# Avometer_v1_2.net
KiCad netlist of a schematic drawn in Altium Designer
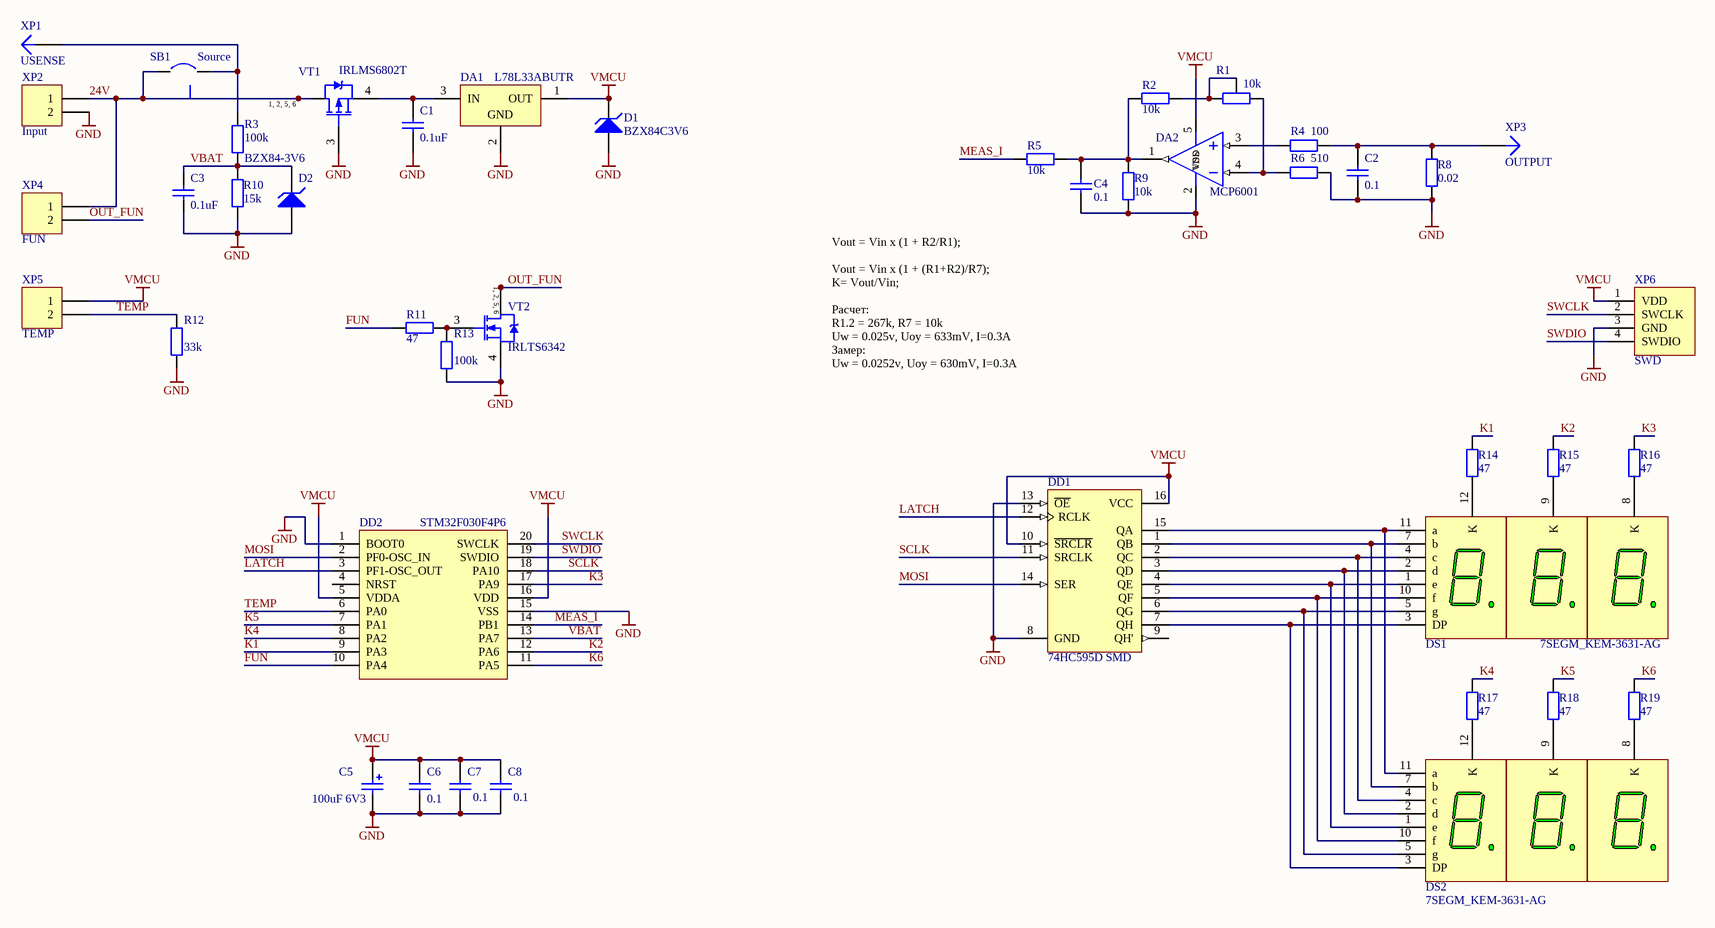
[diagram p0: Avometer v1.2.SchDoc]

(export (version "E")
  (design (tool "Eeschema 10.0.6"))
  (components
    (comp (ref "C1")
      (value "0.1uF")
      (footprint "CAP 0603_N")
      (description "Capacitor SMD")
      (libsource (lib "MyLibrary") (part "CAP_SMD"))
    )
    (comp (ref "C2")
      (value "0.1")
      (footprint "CAP 0603_N")
      (description "Capacitor SMD")
      (libsource (lib "MyLibrary") (part "CAP_SMD"))
    )
    (comp (ref "C3") (value "0.1uF") (footprint "CAP 0603_N") (libsource (lib "") (part "CAP_SMD_1")))
    (comp (ref "C4")
      (value "0.1")
      (footprint "CAP 0603_N")
      (description "Capacitor SMD")
      (libsource (lib "MyLibrary") (part "CAP_SMD"))
    )
    (comp (ref "C5")
      (value "100uF 6V3")
      (footprint "CAP_TANT_B_TYPE_3528-21")
      (description "Capacitor SMD Tantalum")
      (libsource (lib "MyLibrary") (part "CAP_SMD_TANT"))
    )
    (comp (ref "C6")
      (value "0.1")
      (footprint "CAP 0603_N")
      (description "Capacitor SMD")
      (libsource (lib "MyLibrary") (part "CAP_SMD"))
    )
    (comp (ref "C7")
      (value "0.1")
      (footprint "CAP 0603_N")
      (description "Capacitor SMD")
      (libsource (lib "MyLibrary") (part "CAP_SMD"))
    )
    (comp (ref "C8")
      (value "0.1")
      (footprint "CAP 0603_N")
      (description "Capacitor SMD")
      (libsource (lib "MyLibrary") (part "CAP_SMD"))
    )
    (comp (ref "D1")
      (value "BZX84C3V6")
      (footprint "SOT-23_L")
      (description "Zener Diode")
      (fields (field (name "PUBLISHER") "Altium Limited"))
      (libsource (lib "") (part "BZX84_1"))
    )
    (comp (ref "D2")
      (value "BZX84-3V6")
      (footprint "SOT-23_L")
      (description "Zener Diode")
      (fields (field (name "PUBLISHER") "Altium Limited"))
      (libsource (lib "MyLibrary") (part "BZX84"))
    )
    (comp (ref "DA1")
      (value "L78L33ABUTR")
      (footprint "SOT-89")
      (description "Vin=30V Positive Voltage Regulator")
      (fields (field (name "PUBLISHER") "Altium Limited"))
      (libsource (lib "MyLibrary") (part "L78L33ABUTR"))
    )
    (comp (ref "DA2")
      (value "MCP6001")
      (footprint "SOT-23-5_L")
      (description "1 MHz, Low-Power Op Amp")
      (libsource (lib "MyLibrary") (part "MCP6001"))
    )
    (comp (ref "DD1")
      (value "74HC595D SMD")
      (footprint "SOIC-16_L")
      (description "8-Bit Shift Register with 3-State Output Registers")
      (fields (field (name "PUBLISHER") "Altium Limited"))
      (libsource (lib "MyLibrary") (part "74HC595D SMD"))
    )
    (comp (ref "DD2")
      (value "STM32F030F4P6")
      (footprint "TSSOP-20_N")
      (description "Cortex-M0 32-bit MCU, 16 KB Flash, 4 KB Internal RAM, 15 I/Os, 20-pin TSSOP, -40 to 85 degC")
      (libsource (lib "MyLibrary") (part "STM32F030F4P6"))
    )
    (comp (ref "DS1")
      (value "7SEGM_KEM-3631-AG")
      (footprint "7SEGM_KEM-3631-AG_BLUE")
      (description "7.62 mm Black Surface Green 7-Segment Display: CC, RH DP")
      (fields (field (name "PUBLISHER") "Altium Limited"))
      (libsource (lib "MyLibrary") (part "7SEGM_KEM-3631-AG"))
    )
    (comp (ref "DS2")
      (value "7SEGM_KEM-3631-AG")
      (footprint "7SEGM_KEM-3631-AG_RED")
      (description "7.62 mm Black Surface Green 7-Segment Display: CC, RH DP")
      (fields (field (name "PUBLISHER") "Altium Limited"))
      (libsource (lib "MyLibrary") (part "7SEGM_KEM-3631-AG"))
    )
    (comp (ref "R1")
      (value "10k")
      (footprint "RES VAR 1")
      (description "Tapped Resistor")
      (fields (field (name "PUBLISHER") "Altium Limited"))
      (libsource (lib "MyLibrary") (part "RES_SMD_Tap"))
    )
    (comp (ref "R2") (value "10k") (footprint "RES 0603_N") (libsource (lib "") (part "Resistor_SMD_1")))
    (comp (ref "R3") (value "100k") (footprint "RES 0603_N") (libsource (lib "MyLibrary") (part "RES_SMD")))
    (comp (ref "R4") (value "100") (footprint "RES 0603_N") (libsource (lib "") (part "Resistor_SMD_1")))
    (comp (ref "R5")
      (value "10k")
      (footprint "RES 0603_N")
      (description "Resistor")
      (libsource (lib "") (part "RES_SMD_1"))
    )
    (comp (ref "R6") (value "510") (footprint "RES 0603_N") (libsource (lib "") (part "Resistor_SMD_1")))
    (comp (ref "R8")
      (value "0.02")
      (footprint "RES 2512")
      (description "Resistor")
      (libsource (lib "MyLibrary") (part "RES_SMD"))
    )
    (comp (ref "R9") (value "10k") (footprint "RES 0603_N") (libsource (lib "") (part "Resistor_SMD_2")))
    (comp (ref "R10") (value "15k") (footprint "RES 0603_N") (libsource (lib "MyLibrary") (part "RES_SMD")))
    (comp (ref "R11")
      (value "47")
      (footprint "RES 0603_N")
      (description "Chip Resistor")
      (libsource (lib "") (part "RES_SMD_1"))
    )
    (comp (ref "R12")
      (value "33k")
      (footprint "RES 0603_N")
      (description "Chip Resistor")
      (libsource (lib "SyntecoLibrary") (part "RES_SMD"))
    )
    (comp (ref "R13")
      (value "100k")
      (footprint "RES 0603_N")
      (description "Chip Resistor")
      (libsource (lib "SyntecoLibrary") (part "RES_SMD"))
    )
    (comp (ref "R14")
      (value "47")
      (footprint "RES 0603_N")
      (libsource (lib "MyLibrary") (part "Resistor_SMD"))
    )
    (comp (ref "R15")
      (value "47")
      (footprint "RES 0603_N")
      (libsource (lib "MyLibrary") (part "Resistor_SMD"))
    )
    (comp (ref "R16")
      (value "47")
      (footprint "RES 0603_N")
      (libsource (lib "MyLibrary") (part "Resistor_SMD"))
    )
    (comp (ref "R17")
      (value "47")
      (footprint "RES 0603_N")
      (libsource (lib "MyLibrary") (part "Resistor_SMD"))
    )
    (comp (ref "R18")
      (value "47")
      (footprint "RES 0603_N")
      (libsource (lib "MyLibrary") (part "Resistor_SMD"))
    )
    (comp (ref "R19")
      (value "47")
      (footprint "RES 0603_N")
      (libsource (lib "MyLibrary") (part "Resistor_SMD"))
    )
    (comp (ref "SB1")
      (value "Source")
      (footprint "JUMPER_SOLDERED")
      (description "Jumper")
      (libsource (lib "MyLibrary") (part "Jumper_SMD"))
    )
    (comp (ref "VT1")
      (value "IRLMS6802T")
      (footprint "SOT-23-6_L")
      (description "P-Channel MOSFET 20V 4.5A")
      (fields (field (name "PUBLISHER") "Altium Limited"))
      (libsource (lib "MyLibrary") (part "IRLMS6802T"))
    )
    (comp (ref "VT2")
      (value "IRLTS6342")
      (footprint "TSOP-6")
      (description "30V, 6.7A, 1V N-Channel MOSFET")
      (fields (field (name "PUBLISHER") "Altium Limited"))
      (libsource (lib "MyLibrary") (part "IRLTS6342"))
    )
    (comp (ref "XP1")
      (value "USENSE")
      (footprint "CON_PIN")
      (description "Plug papa")
      (fields (field (name "PUBLISHER") "Altium Limited"))
      (libsource (lib "MyLibrary") (part "CON_1x1_PIN"))
    )
    (comp (ref "XP2")
      (value "Input")
      (footprint "CON_5.08MM_1X2")
      (description "Header, 2-Pin")
      (fields (field (name "PUBLISHER") "Altium Limited"))
      (libsource (lib "MyLibrary") (part "CON_5.08mm_1x2"))
    )
    (comp (ref "XP3")
      (value "OUTPUT")
      (footprint "CON_PIN")
      (description "Plug papa")
      (fields (field (name "PUBLISHER") "Altium Limited"))
      (libsource (lib "MyLibrary") (part "CON_1x1_PIN"))
    )
    (comp (ref "XP4")
      (value "FUN")
      (footprint "CON_2.54MM_1X2")
      (description "Header, 2-Pin")
      (fields (field (name "PUBLISHER") "Altium Limited"))
      (libsource (lib "MyLibrary") (part "CON_2.54mm_1x2"))
    )
    (comp (ref "XP5")
      (value "TEMP")
      (footprint "CON_2.54MM_1X2")
      (description "Header, 2-Pin")
      (fields (field (name "PUBLISHER") "Altium Limited"))
      (libsource (lib "MyLibrary") (part "CON_2.54mm_1x2"))
    )
    (comp (ref "XP6")
      (value "SWD")
      (footprint "CON_1.27MM_1X4_SWD")
      (description "Header, 3-Pin")
      (fields (field (name "PUBLISHER") "Altium Limited"))
      (libsource (lib "MyLibrary") (part "CON_1.27mm_1x4_SWD"))
    )
  )
  (nets
    (net (code "1") (name "/24V") (class "Default")
      (node (ref "SB1") (pin "1") (pinfunction "1_1") (pintype "passive"))
      (node (ref "VT1") (pin "1") (pinfunction "D_1") (pintype "passive"))
      (node (ref "VT1") (pin "2") (pinfunction "D_2") (pintype "passive"))
      (node (ref "VT1") (pin "5") (pinfunction "D_5") (pintype "passive"))
      (node (ref "VT1") (pin "6") (pinfunction "D_6") (pintype "passive"))
      (node (ref "XP2") (pin "1") (pinfunction "1_1") (pintype "passive"))
      (node (ref "XP4") (pin "1") (pinfunction "1_1") (pintype "passive"))
    )
    (net (code "2") (name "/FUN") (class "Default")
      (node (ref "DD2") (pin "10") (pinfunction "PA4_10") (pintype "passive"))
      (node (ref "R11") (pin "2") (pinfunction "2_2") (pintype "passive"))
    )
    (net (code "3") (name "/K1") (class "Default")
      (node (ref "DD2") (pin "9") (pinfunction "PA3_9") (pintype "passive"))
      (node (ref "R14") (pin "2") (pinfunction "2_2") (pintype "passive"))
    )
    (net (code "4") (name "/K2") (class "Default")
      (node (ref "DD2") (pin "12") (pinfunction "PA6_12") (pintype "passive"))
      (node (ref "R15") (pin "2") (pinfunction "2_2") (pintype "passive"))
    )
    (net (code "5") (name "/K3") (class "Default")
      (node (ref "DD2") (pin "17") (pinfunction "PA9_17") (pintype "passive"))
      (node (ref "R16") (pin "2") (pinfunction "2_2") (pintype "passive"))
    )
    (net (code "6") (name "/K4") (class "Default")
      (node (ref "DD2") (pin "8") (pinfunction "PA2_8") (pintype "passive"))
      (node (ref "R17") (pin "2") (pinfunction "2_2") (pintype "passive"))
    )
    (net (code "7") (name "/K5") (class "Default")
      (node (ref "DD2") (pin "7") (pinfunction "PA1_7") (pintype "passive"))
      (node (ref "R18") (pin "2") (pinfunction "2_2") (pintype "passive"))
    )
    (net (code "8") (name "/K6") (class "Default")
      (node (ref "DD2") (pin "11") (pinfunction "PA5_11") (pintype "passive"))
      (node (ref "R19") (pin "2") (pinfunction "2_2") (pintype "passive"))
    )
    (net (code "9") (name "/LATCH") (class "Default")
      (node (ref "DD1") (pin "12") (pinfunction "RCLK_12") (pintype "input"))
      (node (ref "DD2") (pin "3") (pinfunction "PF1-OSC_OUT_3") (pintype "passive"))
    )
    (net (code "10") (name "/MEAS_I") (class "Default")
      (node (ref "DD2") (pin "14") (pinfunction "PB1_14") (pintype "passive"))
      (node (ref "R5") (pin "1") (pinfunction "1_1") (pintype "passive"))
    )
    (net (code "11") (name "/MOSI") (class "Default")
      (node (ref "DD1") (pin "14") (pinfunction "SER_14") (pintype "input"))
      (node (ref "DD2") (pin "2") (pinfunction "PF0-OSC_IN_2") (pintype "passive"))
    )
    (net (code "12") (name "/OUT_FUN") (class "Default")
      (node (ref "VT2") (pin "1") (pinfunction "D_1") (pintype "passive"))
      (node (ref "VT2") (pin "2") (pinfunction "D_2") (pintype "passive"))
      (node (ref "VT2") (pin "5") (pinfunction "D_5") (pintype "passive"))
      (node (ref "VT2") (pin "6") (pinfunction "D_6") (pintype "passive"))
      (node (ref "XP4") (pin "2") (pinfunction "2_2") (pintype "passive"))
    )
    (net (code "13") (name "/SCLK") (class "Default")
      (node (ref "DD1") (pin "11") (pinfunction "SRCLK_11") (pintype "input"))
      (node (ref "DD2") (pin "18") (pinfunction "PA10_18") (pintype "passive"))
    )
    (net (code "14") (name "/SWCLK") (class "Default")
      (node (ref "DD2") (pin "20") (pinfunction "SWCLK_20") (pintype "passive"))
      (node (ref "XP6") (pin "2") (pinfunction "SWCLK_2") (pintype "passive"))
    )
    (net (code "15") (name "/SWDIO") (class "Default")
      (node (ref "DD2") (pin "19") (pinfunction "SWDIO_19") (pintype "passive"))
      (node (ref "XP6") (pin "4") (pinfunction "SWDIO_4") (pintype "passive"))
    )
    (net (code "16") (name "/TEMP") (class "Default")
      (node (ref "DD2") (pin "6") (pinfunction "PA0_6") (pintype "passive"))
      (node (ref "R12") (pin "2") (pinfunction "2_2") (pintype "passive"))
      (node (ref "XP5") (pin "2") (pinfunction "2_2") (pintype "passive"))
    )
    (net (code "17") (name "/VBAT") (class "Default")
      (node (ref "C3") (pin "2") (pinfunction "2_2") (pintype "passive"))
      (node (ref "D2") (pin "3") (pinfunction "K_3") (pintype "passive"))
      (node (ref "DD2") (pin "13") (pinfunction "PA7_13") (pintype "passive"))
      (node (ref "R10") (pin "2") (pinfunction "2_2") (pintype "passive"))
      (node (ref "R3") (pin "1") (pinfunction "1_1") (pintype "passive"))
    )
    (net (code "18") (name "GND") (class "Default")
      (node (ref "C1") (pin "1") (pinfunction "1_1") (pintype "passive"))
      (node (ref "C2") (pin "1") (pinfunction "1_1") (pintype "passive"))
      (node (ref "C3") (pin "1") (pinfunction "1_1") (pintype "passive"))
      (node (ref "C4") (pin "1") (pinfunction "1_1") (pintype "passive"))
      (node (ref "C5") (pin "2") (pinfunction "2_2") (pintype "passive"))
      (node (ref "C6") (pin "1") (pinfunction "1_1") (pintype "passive"))
      (node (ref "C7") (pin "2") (pinfunction "2_2") (pintype "passive"))
      (node (ref "C8") (pin "2") (pinfunction "2_2") (pintype "passive"))
      (node (ref "D1") (pin "1") (pinfunction "A_1") (pintype "passive"))
      (node (ref "D2") (pin "1") (pinfunction "A_1") (pintype "passive"))
      (node (ref "DA1") (pin "2") (pinfunction "GND_2") (pintype "power_in"))
      (node (ref "DA2") (pin "2") (pinfunction "VSS_2") (pintype "power_in"))
      (node (ref "DD1") (pin "13") (pinfunction "~{OE}_13") (pintype "input"))
      (node (ref "DD1") (pin "8") (pinfunction "GND_8") (pintype "power_in"))
      (node (ref "DD2") (pin "1") (pinfunction "BOOT0_1") (pintype "passive"))
      (node (ref "DD2") (pin "15") (pinfunction "VSS_15") (pintype "passive"))
      (node (ref "R10") (pin "1") (pinfunction "1_1") (pintype "passive"))
      (node (ref "R12") (pin "1") (pinfunction "1_1") (pintype "passive"))
      (node (ref "R13") (pin "1") (pinfunction "1_1") (pintype "passive"))
      (node (ref "R6") (pin "1") (pinfunction "1_1") (pintype "passive"))
      (node (ref "R8") (pin "1") (pinfunction "1_1") (pintype "passive"))
      (node (ref "R9") (pin "1") (pinfunction "1_1") (pintype "passive"))
      (node (ref "VT1") (pin "3") (pinfunction "G_3") (pintype "passive"))
      (node (ref "VT2") (pin "4") (pinfunction "S_4") (pintype "passive"))
      (node (ref "XP2") (pin "2") (pinfunction "2_2") (pintype "passive"))
      (node (ref "XP6") (pin "3") (pinfunction "GND_3") (pintype "passive"))
    )
    (net (code "19") (name "Net-(C2-Pad2)") (class "Default")
      (node (ref "C2") (pin "2") (pinfunction "2_2") (pintype "passive"))
      (node (ref "R4") (pin "1") (pinfunction "1_1") (pintype "passive"))
      (node (ref "R8") (pin "2") (pinfunction "2_2") (pintype "passive"))
      (node (ref "XP3") (pin "1") (pinfunction "1_1") (pintype "passive"))
    )
    (net (code "20") (name "Net-(DA1-IN)") (class "Default")
      (node (ref "C1") (pin "2") (pinfunction "2_2") (pintype "passive"))
      (node (ref "DA1") (pin "3") (pinfunction "IN_3") (pintype "power_in"))
      (node (ref "VT1") (pin "4") (pinfunction "S_4") (pintype "passive"))
    )
    (net (code "21") (name "Net-(DA2-VIN+)") (class "Default")
      (node (ref "DA2") (pin "3") (pinfunction "VIN+_3") (pintype "input"))
      (node (ref "R4") (pin "2") (pinfunction "2_2") (pintype "passive"))
    )
    (net (code "22") (name "Net-(DA2-VIN-)") (class "Default")
      (node (ref "DA2") (pin "4") (pinfunction "VIN-_4") (pintype "input"))
      (node (ref "R1") (pin "3") (pinfunction "B_3") (pintype "passive"))
      (node (ref "R6") (pin "2") (pinfunction "2_2") (pintype "passive"))
    )
    (net (code "23") (name "Net-(DA2-VOUT)") (class "Default")
      (node (ref "C4") (pin "2") (pinfunction "2_2") (pintype "passive"))
      (node (ref "DA2") (pin "1") (pinfunction "VOUT_1") (pintype "output"))
      (node (ref "R2") (pin "2") (pinfunction "2_2") (pintype "passive"))
      (node (ref "R5") (pin "2") (pinfunction "2_2") (pintype "passive"))
      (node (ref "R9") (pin "2") (pinfunction "2_2") (pintype "passive"))
    )
    (net (code "24") (name "Net-(DD1-QA)") (class "Default")
      (node (ref "DD1") (pin "15") (pinfunction "QA_15") (pintype "tri_state"))
      (node (ref "DS1") (pin "11") (pinfunction "a_11") (pintype "passive"))
      (node (ref "DS2") (pin "11") (pinfunction "a_11") (pintype "passive"))
    )
    (net (code "25") (name "Net-(DD1-QB)") (class "Default")
      (node (ref "DD1") (pin "1") (pinfunction "QB_1") (pintype "tri_state"))
      (node (ref "DS1") (pin "7") (pinfunction "b_7") (pintype "passive"))
      (node (ref "DS2") (pin "7") (pinfunction "b_7") (pintype "passive"))
    )
    (net (code "26") (name "Net-(DD1-QC)") (class "Default")
      (node (ref "DD1") (pin "2") (pinfunction "QC_2") (pintype "tri_state"))
      (node (ref "DS1") (pin "4") (pinfunction "c_4") (pintype "passive"))
      (node (ref "DS2") (pin "4") (pinfunction "c_4") (pintype "passive"))
    )
    (net (code "27") (name "Net-(DD1-QD)") (class "Default")
      (node (ref "DD1") (pin "3") (pinfunction "QD_3") (pintype "tri_state"))
      (node (ref "DS1") (pin "2") (pinfunction "d_2") (pintype "passive"))
      (node (ref "DS2") (pin "2") (pinfunction "d_2") (pintype "passive"))
    )
    (net (code "28") (name "Net-(DD1-QE)") (class "Default")
      (node (ref "DD1") (pin "4") (pinfunction "QE_4") (pintype "tri_state"))
      (node (ref "DS1") (pin "1") (pinfunction "e_1") (pintype "passive"))
      (node (ref "DS2") (pin "1") (pinfunction "e_1") (pintype "passive"))
    )
    (net (code "29") (name "Net-(DD1-QF)") (class "Default")
      (node (ref "DD1") (pin "5") (pinfunction "QF_5") (pintype "tri_state"))
      (node (ref "DS1") (pin "10") (pinfunction "f_10") (pintype "passive"))
      (node (ref "DS2") (pin "10") (pinfunction "f_10") (pintype "passive"))
    )
    (net (code "30") (name "Net-(DD1-QG)") (class "Default")
      (node (ref "DD1") (pin "6") (pinfunction "QG_6") (pintype "tri_state"))
      (node (ref "DS1") (pin "5") (pinfunction "g_5") (pintype "passive"))
      (node (ref "DS2") (pin "5") (pinfunction "g_5") (pintype "passive"))
    )
    (net (code "31") (name "Net-(DD1-QH)") (class "Default")
      (node (ref "DD1") (pin "7") (pinfunction "QH_7") (pintype "tri_state"))
      (node (ref "DS1") (pin "3") (pinfunction "DP_3") (pintype "passive"))
      (node (ref "DS2") (pin "3") (pinfunction "DP_3") (pintype "passive"))
    )
    (net (code "32") (name "Net-(DS1-K-Pad8)") (class "Default")
      (node (ref "DS1") (pin "8") (pinfunction "K_8") (pintype "passive"))
      (node (ref "R16") (pin "1") (pinfunction "1_1") (pintype "passive"))
    )
    (net (code "33") (name "Net-(DS1-K-Pad9)") (class "Default")
      (node (ref "DS1") (pin "9") (pinfunction "K_9") (pintype "passive"))
      (node (ref "R15") (pin "1") (pinfunction "1_1") (pintype "passive"))
    )
    (net (code "34") (name "Net-(DS1-K-Pad12)") (class "Default")
      (node (ref "DS1") (pin "12") (pinfunction "K_12") (pintype "passive"))
      (node (ref "R14") (pin "1") (pinfunction "1_1") (pintype "passive"))
    )
    (net (code "35") (name "Net-(DS2-K-Pad8)") (class "Default")
      (node (ref "DS2") (pin "8") (pinfunction "K_8") (pintype "passive"))
      (node (ref "R19") (pin "1") (pinfunction "1_1") (pintype "passive"))
    )
    (net (code "36") (name "Net-(DS2-K-Pad9)") (class "Default")
      (node (ref "DS2") (pin "9") (pinfunction "K_9") (pintype "passive"))
      (node (ref "R18") (pin "1") (pinfunction "1_1") (pintype "passive"))
    )
    (net (code "37") (name "Net-(DS2-K-Pad12)") (class "Default")
      (node (ref "DS2") (pin "12") (pinfunction "K_12") (pintype "passive"))
      (node (ref "R17") (pin "1") (pinfunction "1_1") (pintype "passive"))
    )
    (net (code "38") (name "Net-(R1-A)") (class "Default")
      (node (ref "R1") (pin "1") (pinfunction "A_1") (pintype "passive"))
      (node (ref "R1") (pin "2") (pinfunction "TAP_2") (pintype "passive"))
      (node (ref "R2") (pin "1") (pinfunction "1_1") (pintype "passive"))
    )
    (net (code "39") (name "Net-(R3-Pad2)") (class "Default")
      (node (ref "R3") (pin "2") (pinfunction "2_2") (pintype "passive"))
      (node (ref "SB1") (pin "2") (pinfunction "2_2") (pintype "passive"))
      (node (ref "XP1") (pin "1") (pinfunction "1_1") (pintype "passive"))
    )
    (net (code "40") (name "Net-(VT2-G)") (class "Default")
      (node (ref "R11") (pin "1") (pinfunction "1_1") (pintype "passive"))
      (node (ref "R13") (pin "2") (pinfunction "2_2") (pintype "passive"))
      (node (ref "VT2") (pin "3") (pinfunction "G_3") (pintype "passive"))
    )
    (net (code "41") (name "VMCU") (class "Default")
      (node (ref "C5") (pin "1") (pinfunction "1_1") (pintype "passive"))
      (node (ref "C6") (pin "2") (pinfunction "2_2") (pintype "passive"))
      (node (ref "C7") (pin "1") (pinfunction "1_1") (pintype "passive"))
      (node (ref "C8") (pin "1") (pinfunction "1_1") (pintype "passive"))
      (node (ref "D1") (pin "3") (pinfunction "K_3") (pintype "passive"))
      (node (ref "DA1") (pin "1") (pinfunction "OUT_1") (pintype "power_in"))
      (node (ref "DA2") (pin "5") (pinfunction "VDD_5") (pintype "power_in"))
      (node (ref "DD1") (pin "10") (pinfunction "~{SRCLR}_10") (pintype "input"))
      (node (ref "DD1") (pin "16") (pinfunction "VCC_16") (pintype "power_in"))
      (node (ref "DD2") (pin "16") (pinfunction "VDD_16") (pintype "passive"))
      (node (ref "DD2") (pin "5") (pinfunction "VDDA_5") (pintype "passive"))
      (node (ref "XP5") (pin "1") (pinfunction "1_1") (pintype "passive"))
      (node (ref "XP6") (pin "1") (pinfunction "VDD_1") (pintype "passive"))
    )
    (net (code "42") (name "unconnected-(DD1-QH'-Pad9)") (class "Default")
      (node (ref "DD1") (pin "9") (pinfunction "QH'_9") (pintype "output"))
    )
    (net (code "43") (name "unconnected-(DD2-NRST-Pad4)") (class "Default")
      (node (ref "DD2") (pin "4") (pinfunction "NRST_4") (pintype "passive"))
    )
  )
)
